# pure_midi.net
KiCad netlist of a schematic drawn in EAGLE
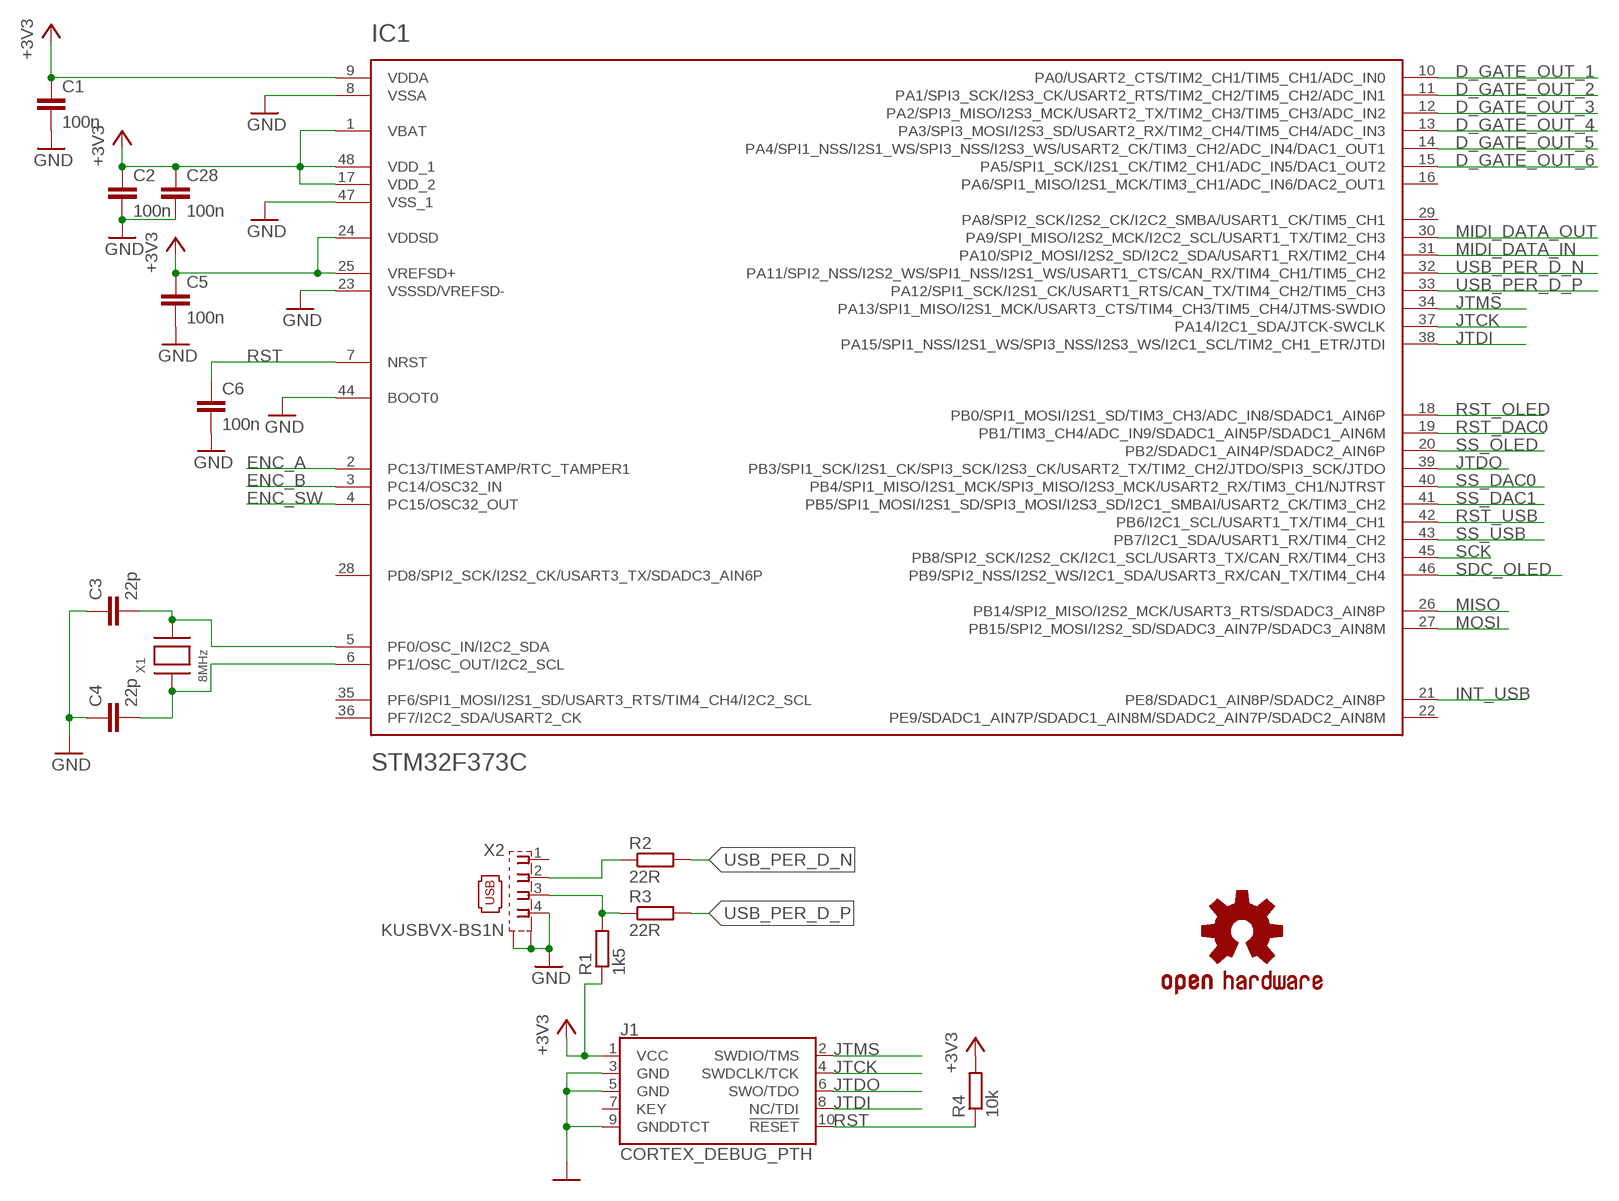
[diagram p0: schematic, sheet 1]
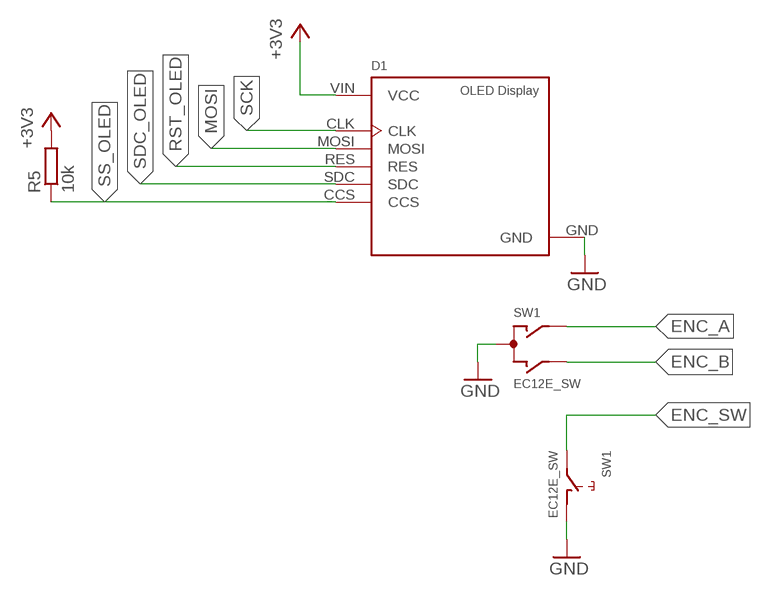
[diagram p1: schematic, sheet 2]
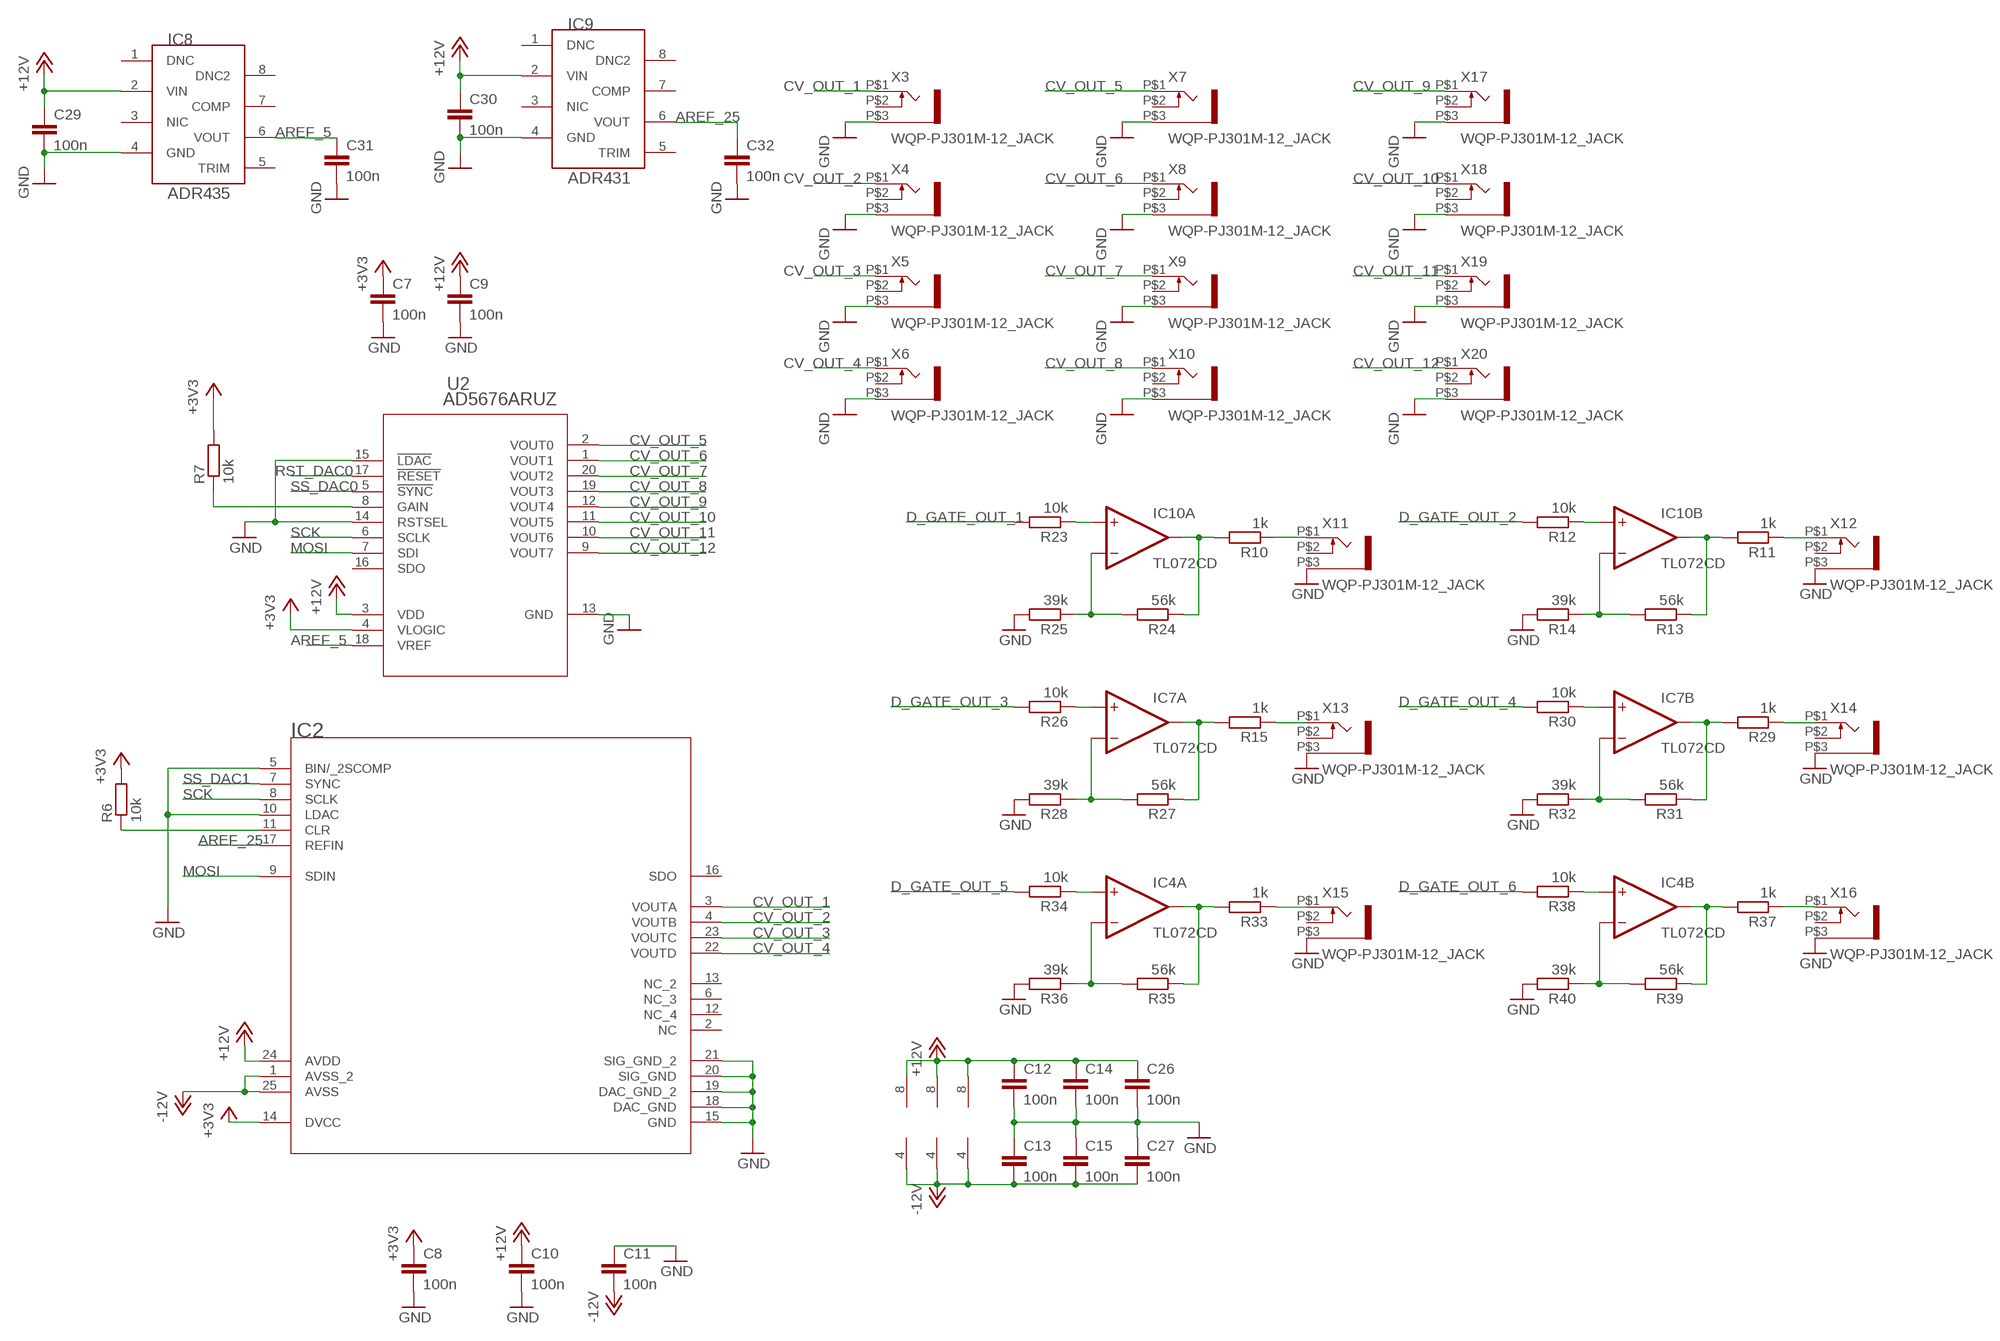
[diagram p2: schematic, sheet 3]
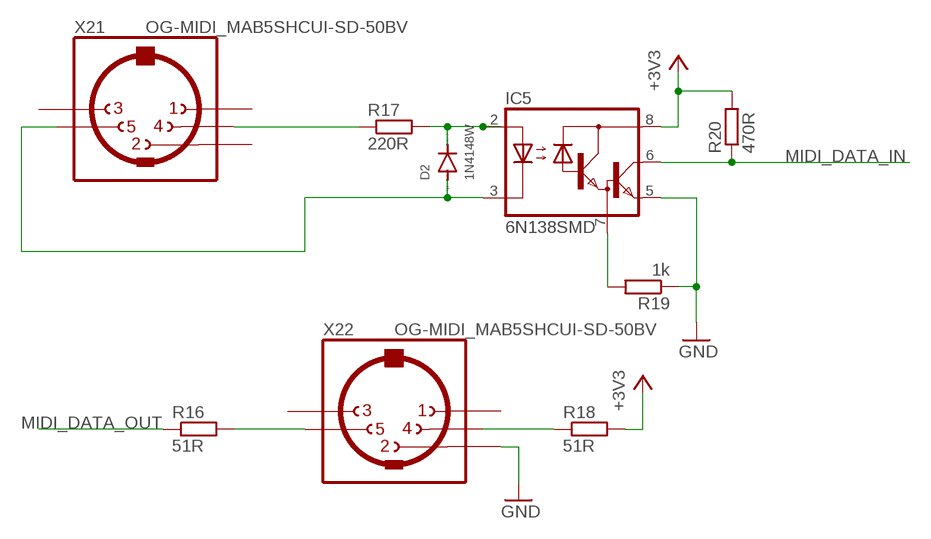
[diagram p3: schematic, sheet 4]
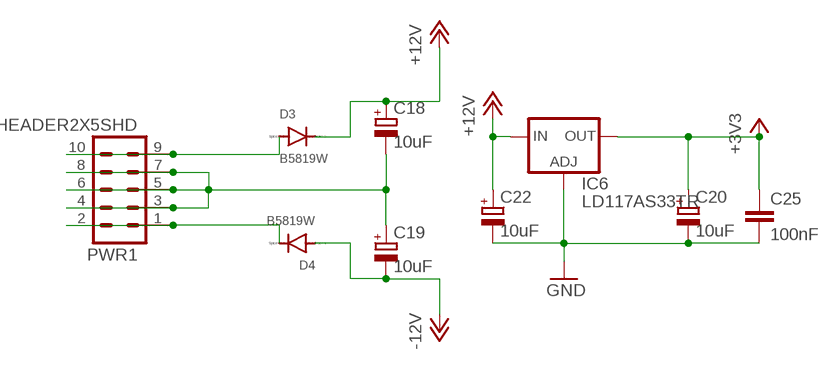
[diagram p4: schematic, sheet 5]

(export (version "E")
  (design (tool "Eeschema 10.0.6"))
  (components
    (comp (ref "C1")
      (value "100n")
      (footprint "eagle-import:C0603")
      (libsource (lib "eagle-import") (part "C-EUC0603"))
    )
    (comp (ref "C2")
      (value "100n")
      (footprint "eagle-import:C0603")
      (libsource (lib "eagle-import") (part "C-EUC0603"))
    )
    (comp (ref "C3")
      (value "22p")
      (footprint "eagle-import:C0603")
      (libsource (lib "eagle-import") (part "C-EUC0603"))
    )
    (comp (ref "C4")
      (value "22p")
      (footprint "eagle-import:C0603")
      (libsource (lib "eagle-import") (part "C-EUC0603"))
    )
    (comp (ref "C5")
      (value "100n")
      (footprint "eagle-import:C0603")
      (libsource (lib "eagle-import") (part "C-EUC0603"))
    )
    (comp (ref "C6")
      (value "100n")
      (footprint "eagle-import:C0603")
      (libsource (lib "eagle-import") (part "C-EUC0603"))
    )
    (comp (ref "C28")
      (value "100n")
      (footprint "eagle-import:C0603")
      (libsource (lib "eagle-import") (part "C-EUC0603"))
    )
    (comp (ref "IC1")
      (value "STM32F373C")
      (footprint "eagle-import:LQFP48")
      (libsource (lib "eagle-import") (part "STM32F373C"))
    )
    (comp (ref "J1")
      (value "CORTEX_DEBUG_PTH")
      (footprint "eagle-import:2X5-PTH-1.27MM")
      (libsource (lib "eagle-import") (part "CORTEX_DEBUG_PTH"))
    )
    (comp (ref "LOGO1")
      (value "OSHW-LOGOM")
      (footprint "eagle-import:OSHW-LOGO-M")
      (libsource (lib "eagle-import") (part "OSHW-LOGOM"))
    )
    (comp (ref "R1")
      (value "1k5")
      (footprint "eagle-import:R0603")
      (libsource (lib "eagle-import") (part "R-EU_R0603"))
    )
    (comp (ref "R2")
      (value "22R")
      (footprint "eagle-import:R0603")
      (libsource (lib "eagle-import") (part "R-EU_R0603"))
    )
    (comp (ref "R3")
      (value "22R")
      (footprint "eagle-import:R0603")
      (libsource (lib "eagle-import") (part "R-EU_R0603"))
    )
    (comp (ref "R4")
      (value "10k")
      (footprint "eagle-import:R0603")
      (libsource (lib "eagle-import") (part "R-EU_R0603"))
    )
    (comp (ref "X1")
      (value "8MHz")
      (footprint "eagle-import:NX5032")
      (libsource (lib "eagle-import") (part "XTALNX5032"))
    )
    (comp (ref "X2")
      (value "KUSBVX-BS1N")
      (footprint "eagle-import:KUSBVX-BS1N")
      (libsource (lib "eagle-import") (part "KUSBVX-BS1N"))
    )
    (comp (ref "D1")
      (value "OLED_1.3_128X64_SPI")
      (footprint "eagle-import:C1_ADAFRUIT_1.3_128X64_OLED")
      (libsource (lib "eagle-import") (part "OLED_1.3_128X64_SPI"))
    )
    (comp (ref "R5")
      (value "10k")
      (footprint "eagle-import:R0603")
      (libsource (lib "eagle-import") (part "R-EU_R0603"))
    )
    (comp (ref "SW1")
      (value "EC12E_SW")
      (footprint "eagle-import:ALPS_EC12E_SW")
      (fields (field (name "MPN") "EC12E2424407"))
      (libsource (lib "eagle-import") (part "EC12E_SW"))
    )
    (comp (ref "C7")
      (value "100n")
      (footprint "eagle-import:C0603")
      (libsource (lib "eagle-import") (part "C-EUC0603"))
    )
    (comp (ref "C8")
      (value "100n")
      (footprint "eagle-import:C0603")
      (libsource (lib "eagle-import") (part "C-EUC0603"))
    )
    (comp (ref "C9")
      (value "100n")
      (footprint "eagle-import:C0603")
      (libsource (lib "eagle-import") (part "C-EUC0603"))
    )
    (comp (ref "C10")
      (value "100n")
      (footprint "eagle-import:C0603")
      (libsource (lib "eagle-import") (part "C-EUC0603"))
    )
    (comp (ref "C11")
      (value "100n")
      (footprint "eagle-import:C0603")
      (libsource (lib "eagle-import") (part "C-EUC0603"))
    )
    (comp (ref "C12")
      (value "100n")
      (footprint "eagle-import:C0603")
      (libsource (lib "eagle-import") (part "C-EUC0603"))
    )
    (comp (ref "C13")
      (value "100n")
      (footprint "eagle-import:C0603")
      (libsource (lib "eagle-import") (part "C-EUC0603"))
    )
    (comp (ref "C14")
      (value "100n")
      (footprint "eagle-import:C0603")
      (libsource (lib "eagle-import") (part "C-EUC0603"))
    )
    (comp (ref "C15")
      (value "100n")
      (footprint "eagle-import:C0603")
      (libsource (lib "eagle-import") (part "C-EUC0603"))
    )
    (comp (ref "C26")
      (value "100n")
      (footprint "eagle-import:C0603")
      (libsource (lib "eagle-import") (part "C-EUC0603"))
    )
    (comp (ref "C27")
      (value "100n")
      (footprint "eagle-import:C0603")
      (libsource (lib "eagle-import") (part "C-EUC0603"))
    )
    (comp (ref "C29")
      (value "100n")
      (footprint "eagle-import:C0603")
      (libsource (lib "eagle-import") (part "C-EUC0603"))
    )
    (comp (ref "C30")
      (value "100n")
      (footprint "eagle-import:C0603")
      (libsource (lib "eagle-import") (part "C-EUC0603"))
    )
    (comp (ref "C31")
      (value "100n")
      (footprint "eagle-import:C0603")
      (libsource (lib "eagle-import") (part "C-EUC0603"))
    )
    (comp (ref "C32")
      (value "100n")
      (footprint "eagle-import:C0603")
      (libsource (lib "eagle-import") (part "C-EUC0603"))
    )
    (comp (ref "IC2")
      (value "AD5754BREZ")
      (footprint "eagle-import:RE_24")
      (libsource (lib "eagle-import") (part "AD5754BREZ"))
    )
    (comp (ref "IC4")
      (value "TL072CD")
      (footprint "eagle-import:SOIC8")
      (libsource (lib "eagle-import") (part "TL072DC"))
    )
    (comp (ref "IC7")
      (value "TL072CD")
      (footprint "eagle-import:SOIC8")
      (libsource (lib "eagle-import") (part "TL072DC"))
    )
    (comp (ref "IC8")
      (value "ADR435")
      (footprint "eagle-import:MSOP8")
      (libsource (lib "eagle-import") (part "ADR43XXRMZ"))
    )
    (comp (ref "IC9")
      (value "ADR431")
      (footprint "eagle-import:MSOP8")
      (libsource (lib "eagle-import") (part "ADR43XXRMZ"))
    )
    (comp (ref "IC10")
      (value "TL072CD")
      (footprint "eagle-import:SOIC8")
      (libsource (lib "eagle-import") (part "TL072DC"))
    )
    (comp (ref "R6")
      (value "10k")
      (footprint "eagle-import:R0603")
      (libsource (lib "eagle-import") (part "R-EU_R0603"))
    )
    (comp (ref "R7")
      (value "10k")
      (footprint "eagle-import:R0603")
      (libsource (lib "eagle-import") (part "R-EU_R0603"))
    )
    (comp (ref "R10")
      (value "1k")
      (footprint "eagle-import:R0603")
      (libsource (lib "eagle-import") (part "R-EU_R0603"))
    )
    (comp (ref "R11")
      (value "1k")
      (footprint "eagle-import:R0603")
      (libsource (lib "eagle-import") (part "R-EU_R0603"))
    )
    (comp (ref "R12")
      (value "10k")
      (footprint "eagle-import:R0603")
      (libsource (lib "eagle-import") (part "R-EU_R0603"))
    )
    (comp (ref "R13")
      (value "56k")
      (footprint "eagle-import:R0603")
      (libsource (lib "eagle-import") (part "R-EU_R0603"))
    )
    (comp (ref "R14")
      (value "39k")
      (footprint "eagle-import:R0603")
      (libsource (lib "eagle-import") (part "R-EU_R0603"))
    )
    (comp (ref "R15")
      (value "1k")
      (footprint "eagle-import:R0603")
      (libsource (lib "eagle-import") (part "R-EU_R0603"))
    )
    (comp (ref "R23")
      (value "10k")
      (footprint "eagle-import:R0603")
      (libsource (lib "eagle-import") (part "R-EU_R0603"))
    )
    (comp (ref "R24")
      (value "56k")
      (footprint "eagle-import:R0603")
      (libsource (lib "eagle-import") (part "R-EU_R0603"))
    )
    (comp (ref "R25")
      (value "39k")
      (footprint "eagle-import:R0603")
      (libsource (lib "eagle-import") (part "R-EU_R0603"))
    )
    (comp (ref "R26")
      (value "10k")
      (footprint "eagle-import:R0603")
      (libsource (lib "eagle-import") (part "R-EU_R0603"))
    )
    (comp (ref "R27")
      (value "56k")
      (footprint "eagle-import:R0603")
      (libsource (lib "eagle-import") (part "R-EU_R0603"))
    )
    (comp (ref "R28")
      (value "39k")
      (footprint "eagle-import:R0603")
      (libsource (lib "eagle-import") (part "R-EU_R0603"))
    )
    (comp (ref "R29")
      (value "1k")
      (footprint "eagle-import:R0603")
      (libsource (lib "eagle-import") (part "R-EU_R0603"))
    )
    (comp (ref "R30")
      (value "10k")
      (footprint "eagle-import:R0603")
      (libsource (lib "eagle-import") (part "R-EU_R0603"))
    )
    (comp (ref "R31")
      (value "56k")
      (footprint "eagle-import:R0603")
      (libsource (lib "eagle-import") (part "R-EU_R0603"))
    )
    (comp (ref "R32")
      (value "39k")
      (footprint "eagle-import:R0603")
      (libsource (lib "eagle-import") (part "R-EU_R0603"))
    )
    (comp (ref "R33")
      (value "1k")
      (footprint "eagle-import:R0603")
      (libsource (lib "eagle-import") (part "R-EU_R0603"))
    )
    (comp (ref "R34")
      (value "10k")
      (footprint "eagle-import:R0603")
      (libsource (lib "eagle-import") (part "R-EU_R0603"))
    )
    (comp (ref "R35")
      (value "56k")
      (footprint "eagle-import:R0603")
      (libsource (lib "eagle-import") (part "R-EU_R0603"))
    )
    (comp (ref "R36")
      (value "39k")
      (footprint "eagle-import:R0603")
      (libsource (lib "eagle-import") (part "R-EU_R0603"))
    )
    (comp (ref "R37")
      (value "1k")
      (footprint "eagle-import:R0603")
      (libsource (lib "eagle-import") (part "R-EU_R0603"))
    )
    (comp (ref "R38")
      (value "10k")
      (footprint "eagle-import:R0603")
      (libsource (lib "eagle-import") (part "R-EU_R0603"))
    )
    (comp (ref "R39")
      (value "56k")
      (footprint "eagle-import:R0603")
      (libsource (lib "eagle-import") (part "R-EU_R0603"))
    )
    (comp (ref "R40")
      (value "39k")
      (footprint "eagle-import:R0603")
      (libsource (lib "eagle-import") (part "R-EU_R0603"))
    )
    (comp (ref "U2")
      (value "AD5676ARUZ")
      (footprint "eagle-import:RU_20")
      (libsource (lib "eagle-import") (part "AD5676ARUZ"))
    )
    (comp (ref "X3")
      (value "WQP-PJ301M-12_JACK")
      (footprint "eagle-import:WQP-PJ301M-12_JACK")
      (libsource (lib "eagle-import") (part "WQP-PJ301M-12_JACK"))
    )
    (comp (ref "X4")
      (value "WQP-PJ301M-12_JACK")
      (footprint "eagle-import:WQP-PJ301M-12_JACK")
      (libsource (lib "eagle-import") (part "WQP-PJ301M-12_JACK"))
    )
    (comp (ref "X5")
      (value "WQP-PJ301M-12_JACK")
      (footprint "eagle-import:WQP-PJ301M-12_JACK")
      (libsource (lib "eagle-import") (part "WQP-PJ301M-12_JACK"))
    )
    (comp (ref "X6")
      (value "WQP-PJ301M-12_JACK")
      (footprint "eagle-import:WQP-PJ301M-12_JACK")
      (libsource (lib "eagle-import") (part "WQP-PJ301M-12_JACK"))
    )
    (comp (ref "X7")
      (value "WQP-PJ301M-12_JACK")
      (footprint "eagle-import:WQP-PJ301M-12_JACK")
      (libsource (lib "eagle-import") (part "WQP-PJ301M-12_JACK"))
    )
    (comp (ref "X8")
      (value "WQP-PJ301M-12_JACK")
      (footprint "eagle-import:WQP-PJ301M-12_JACK")
      (libsource (lib "eagle-import") (part "WQP-PJ301M-12_JACK"))
    )
    (comp (ref "X9")
      (value "WQP-PJ301M-12_JACK")
      (footprint "eagle-import:WQP-PJ301M-12_JACK")
      (libsource (lib "eagle-import") (part "WQP-PJ301M-12_JACK"))
    )
    (comp (ref "X10")
      (value "WQP-PJ301M-12_JACK")
      (footprint "eagle-import:WQP-PJ301M-12_JACK")
      (libsource (lib "eagle-import") (part "WQP-PJ301M-12_JACK"))
    )
    (comp (ref "X11")
      (value "WQP-PJ301M-12_JACK")
      (footprint "eagle-import:WQP-PJ301M-12_JACK")
      (libsource (lib "eagle-import") (part "WQP-PJ301M-12_JACK"))
    )
    (comp (ref "X12")
      (value "WQP-PJ301M-12_JACK")
      (footprint "eagle-import:WQP-PJ301M-12_JACK")
      (libsource (lib "eagle-import") (part "WQP-PJ301M-12_JACK"))
    )
    (comp (ref "X13")
      (value "WQP-PJ301M-12_JACK")
      (footprint "eagle-import:WQP-PJ301M-12_JACK")
      (libsource (lib "eagle-import") (part "WQP-PJ301M-12_JACK"))
    )
    (comp (ref "X14")
      (value "WQP-PJ301M-12_JACK")
      (footprint "eagle-import:WQP-PJ301M-12_JACK")
      (libsource (lib "eagle-import") (part "WQP-PJ301M-12_JACK"))
    )
    (comp (ref "X15")
      (value "WQP-PJ301M-12_JACK")
      (footprint "eagle-import:WQP-PJ301M-12_JACK")
      (libsource (lib "eagle-import") (part "WQP-PJ301M-12_JACK"))
    )
    (comp (ref "X16")
      (value "WQP-PJ301M-12_JACK")
      (footprint "eagle-import:WQP-PJ301M-12_JACK")
      (libsource (lib "eagle-import") (part "WQP-PJ301M-12_JACK"))
    )
    (comp (ref "X17")
      (value "WQP-PJ301M-12_JACK")
      (footprint "eagle-import:WQP-PJ301M-12_JACK")
      (libsource (lib "eagle-import") (part "WQP-PJ301M-12_JACK"))
    )
    (comp (ref "X18")
      (value "WQP-PJ301M-12_JACK")
      (footprint "eagle-import:WQP-PJ301M-12_JACK")
      (libsource (lib "eagle-import") (part "WQP-PJ301M-12_JACK"))
    )
    (comp (ref "X19")
      (value "WQP-PJ301M-12_JACK")
      (footprint "eagle-import:WQP-PJ301M-12_JACK")
      (libsource (lib "eagle-import") (part "WQP-PJ301M-12_JACK"))
    )
    (comp (ref "X20")
      (value "WQP-PJ301M-12_JACK")
      (footprint "eagle-import:WQP-PJ301M-12_JACK")
      (libsource (lib "eagle-import") (part "WQP-PJ301M-12_JACK"))
    )
    (comp (ref "D2")
      (value "1N4148W")
      (footprint "eagle-import:SOD123")
      (libsource (lib "eagle-import") (part "DIODE-SOD123"))
    )
    (comp (ref "IC5")
      (value "6N138SMD")
      (footprint "eagle-import:SO8-GW300")
      (libsource (lib "eagle-import") (part "6N138SMD"))
    )
    (comp (ref "R16")
      (value "51R")
      (footprint "eagle-import:R0603")
      (libsource (lib "eagle-import") (part "R-EU_R0603"))
    )
    (comp (ref "R17")
      (value "220R")
      (footprint "eagle-import:R0603")
      (libsource (lib "eagle-import") (part "R-EU_R0603"))
    )
    (comp (ref "R18")
      (value "51R")
      (footprint "eagle-import:R0603")
      (libsource (lib "eagle-import") (part "R-EU_R0603"))
    )
    (comp (ref "R19")
      (value "1k")
      (footprint "eagle-import:R0603")
      (libsource (lib "eagle-import") (part "R-EU_R0603"))
    )
    (comp (ref "R20")
      (value "470R")
      (footprint "eagle-import:R0603")
      (libsource (lib "eagle-import") (part "R-EU_R0603"))
    )
    (comp (ref "X21")
      (value "OG-MIDI_MAB5SHCUI-SD-50BV")
      (footprint "eagle-import:OG-MIDI_SD-50BV")
      (libsource (lib "eagle-import") (part "OG-MIDI_MAB5SHCUI-SD-50BV"))
    )
    (comp (ref "X22")
      (value "OG-MIDI_MAB5SHCUI-SD-50BV")
      (footprint "eagle-import:OG-MIDI_SD-50BV")
      (libsource (lib "eagle-import") (part "OG-MIDI_MAB5SHCUI-SD-50BV"))
    )
    (comp (ref "C18")
      (value "10uF")
      (footprint "eagle-import:CASE-A_3216")
      (libsource (lib "eagle-import") (part "CPOL-EUA/3216-18R"))
    )
    (comp (ref "C19")
      (value "10uF")
      (footprint "eagle-import:CASE-A_3216")
      (libsource (lib "eagle-import") (part "CPOL-EUA/3216-18R"))
    )
    (comp (ref "C20")
      (value "10uF")
      (footprint "eagle-import:CASE-A_3216")
      (libsource (lib "eagle-import") (part "CPOL-EUA/3216-18R"))
    )
    (comp (ref "C22")
      (value "10uF")
      (footprint "eagle-import:CASE-A_3216")
      (libsource (lib "eagle-import") (part "CPOL-EUA/3216-18R"))
    )
    (comp (ref "C25")
      (value "100nF")
      (footprint "eagle-import:C0603")
      (libsource (lib "eagle-import") (part "C-EUC0603"))
    )
    (comp (ref "D3")
      (value "B5819W")
      (footprint "eagle-import:SOD123")
      (libsource (lib "eagle-import") (part "DIODE-SOD123"))
    )
    (comp (ref "D4")
      (value "B5819W")
      (footprint "eagle-import:SOD123")
      (libsource (lib "eagle-import") (part "DIODE-SOD123"))
    )
    (comp (ref "IC6")
      (value "LD117AS33TR")
      (footprint "eagle-import:SOT223")
      (libsource (lib "eagle-import") (part "LD117A?S33TR"))
    )
    (comp (ref "PWR1")
      (value "HEADER2X5SHD")
      (footprint "eagle-import:2X5-SHROUDED")
      (libsource (lib "eagle-import") (part "HEADER2X5SHD"))
    )
  )
  (nets
    (net (code "1") (name "+3V3") (class "Default")
      (node (ref "C1") (pin "1") (pinfunction "1_1") (pintype "passive"))
      (node (ref "C2") (pin "1") (pinfunction "1_1") (pintype "passive"))
      (node (ref "C20") (pin "+") (pinfunction "+_+") (pintype "passive"))
      (node (ref "C25") (pin "1") (pinfunction "1_1") (pintype "passive"))
      (node (ref "C28") (pin "1") (pinfunction "1_1") (pintype "passive"))
      (node (ref "C5") (pin "1") (pinfunction "1_1") (pintype "passive"))
      (node (ref "C7") (pin "1") (pinfunction "1_1") (pintype "passive"))
      (node (ref "C8") (pin "1") (pinfunction "1_1") (pintype "passive"))
      (node (ref "D1") (pin "VIN") (pinfunction "VCC_VIN") (pintype "power_in"))
      (node (ref "IC1") (pin "1") (pinfunction "VBAT_1") (pintype "power_in"))
      (node (ref "IC1") (pin "17") (pinfunction "VDD_2_17") (pintype "power_in"))
      (node (ref "IC1") (pin "24") (pinfunction "VDDSD_24") (pintype "power_in"))
      (node (ref "IC1") (pin "25") (pinfunction "VREFSD+_25") (pintype "power_in"))
      (node (ref "IC1") (pin "48") (pinfunction "VDD_1_48") (pintype "power_in"))
      (node (ref "IC1") (pin "9") (pinfunction "VDDA_9") (pintype "power_in"))
      (node (ref "IC2") (pin "14") (pinfunction "DVCC_14") (pintype "power_in"))
      (node (ref "IC5") (pin "8") (pinfunction "VCC_8") (pintype "passive"))
      (node (ref "IC6") (pin "4") (pinfunction "OUT_4") (pintype "passive"))
      (node (ref "J1") (pin "1") (pinfunction "VCC_1") (pintype "bidirectional"))
      (node (ref "R1") (pin "1") (pinfunction "1_1") (pintype "passive"))
      (node (ref "R18") (pin "2") (pinfunction "2_2") (pintype "passive"))
      (node (ref "R20") (pin "2") (pinfunction "2_2") (pintype "passive"))
      (node (ref "R4") (pin "2") (pinfunction "2_2") (pintype "passive"))
      (node (ref "R5") (pin "2") (pinfunction "2_2") (pintype "passive"))
      (node (ref "R6") (pin "2") (pinfunction "2_2") (pintype "passive"))
      (node (ref "R7") (pin "2") (pinfunction "2_2") (pintype "passive"))
      (node (ref "U2") (pin "4") (pinfunction "VLOGIC_4") (pintype "passive"))
    )
    (net (code "2") (name "+12V") (class "Default")
      (node (ref "C10") (pin "1") (pinfunction "1_1") (pintype "passive"))
      (node (ref "C12") (pin "1") (pinfunction "1_1") (pintype "passive"))
      (node (ref "C14") (pin "1") (pinfunction "1_1") (pintype "passive"))
      (node (ref "C18") (pin "+") (pinfunction "+_+") (pintype "passive"))
      (node (ref "C22") (pin "+") (pinfunction "+_+") (pintype "passive"))
      (node (ref "C26") (pin "1") (pinfunction "1_1") (pintype "passive"))
      (node (ref "C29") (pin "1") (pinfunction "1_1") (pintype "passive"))
      (node (ref "C30") (pin "1") (pinfunction "1_1") (pintype "passive"))
      (node (ref "C9") (pin "1") (pinfunction "1_1") (pintype "passive"))
      (node (ref "D3") (pin "C") (pinfunction "C_C") (pintype "passive"))
      (node (ref "IC10") (pin "8") (pinfunction "V+_8") (pintype "power_in"))
      (node (ref "IC2") (pin "24") (pinfunction "AVDD_24") (pintype "power_in"))
      (node (ref "IC4") (pin "8") (pinfunction "V+_8") (pintype "power_in"))
      (node (ref "IC6") (pin "3") (pinfunction "IN_3") (pintype "input"))
      (node (ref "IC7") (pin "8") (pinfunction "V+_8") (pintype "power_in"))
      (node (ref "IC8") (pin "2") (pinfunction "VIN_2") (pintype "power_in"))
      (node (ref "IC9") (pin "2") (pinfunction "VIN_2") (pintype "power_in"))
      (node (ref "U2") (pin "3") (pinfunction "VDD_3") (pintype "passive"))
    )
    (net (code "3") (name "-12V") (class "Default")
      (node (ref "C11") (pin "2") (pinfunction "2_2") (pintype "passive"))
      (node (ref "C13") (pin "2") (pinfunction "2_2") (pintype "passive"))
      (node (ref "C15") (pin "2") (pinfunction "2_2") (pintype "passive"))
      (node (ref "C19") (pin "-") (pinfunction "-_-") (pintype "passive"))
      (node (ref "C27") (pin "2") (pinfunction "2_2") (pintype "passive"))
      (node (ref "D4") (pin "A") (pinfunction "A_A") (pintype "passive"))
      (node (ref "IC10") (pin "4") (pinfunction "V-_4") (pintype "power_in"))
      (node (ref "IC2") (pin "1") (pinfunction "AVSS_2_1") (pintype "passive"))
      (node (ref "IC2") (pin "25") (pinfunction "AVSS_25") (pintype "power_in"))
      (node (ref "IC4") (pin "4") (pinfunction "V-_4") (pintype "power_in"))
      (node (ref "IC7") (pin "4") (pinfunction "V-_4") (pintype "power_in"))
    )
    (net (code "4") (name "AREF_5") (class "Default")
      (node (ref "C31") (pin "1") (pinfunction "1_1") (pintype "passive"))
      (node (ref "IC8") (pin "6") (pinfunction "VOUT_6") (pintype "power_in"))
      (node (ref "U2") (pin "18") (pinfunction "VREF_18") (pintype "passive"))
    )
    (net (code "5") (name "AREF_25") (class "Default")
      (node (ref "C32") (pin "1") (pinfunction "1_1") (pintype "passive"))
      (node (ref "IC2") (pin "17") (pinfunction "REFIN_17") (pintype "passive"))
      (node (ref "IC9") (pin "6") (pinfunction "VOUT_6") (pintype "power_in"))
    )
    (net (code "6") (name "CV_OUT_1") (class "Default")
      (node (ref "IC2") (pin "3") (pinfunction "VOUTA_3") (pintype "passive"))
      (node (ref "X3") (pin "P$1") (pinfunction "2_P$1") (pintype "passive"))
    )
    (net (code "7") (name "CV_OUT_2") (class "Default")
      (node (ref "IC2") (pin "4") (pinfunction "VOUTB_4") (pintype "passive"))
      (node (ref "X4") (pin "P$1") (pinfunction "2_P$1") (pintype "passive"))
    )
    (net (code "8") (name "CV_OUT_3") (class "Default")
      (node (ref "IC2") (pin "23") (pinfunction "VOUTC_23") (pintype "passive"))
      (node (ref "X5") (pin "P$1") (pinfunction "2_P$1") (pintype "passive"))
    )
    (net (code "9") (name "CV_OUT_4") (class "Default")
      (node (ref "IC2") (pin "22") (pinfunction "VOUTD_22") (pintype "passive"))
      (node (ref "X6") (pin "P$1") (pinfunction "2_P$1") (pintype "passive"))
    )
    (net (code "10") (name "CV_OUT_5") (class "Default")
      (node (ref "U2") (pin "2") (pinfunction "VOUT0_2") (pintype "passive"))
      (node (ref "X7") (pin "P$1") (pinfunction "2_P$1") (pintype "passive"))
    )
    (net (code "11") (name "CV_OUT_6") (class "Default")
      (node (ref "U2") (pin "1") (pinfunction "VOUT1_1") (pintype "passive"))
      (node (ref "X8") (pin "P$1") (pinfunction "2_P$1") (pintype "passive"))
    )
    (net (code "12") (name "CV_OUT_7") (class "Default")
      (node (ref "U2") (pin "20") (pinfunction "VOUT2_20") (pintype "passive"))
      (node (ref "X9") (pin "P$1") (pinfunction "2_P$1") (pintype "passive"))
    )
    (net (code "13") (name "CV_OUT_8") (class "Default")
      (node (ref "U2") (pin "19") (pinfunction "VOUT3_19") (pintype "passive"))
      (node (ref "X10") (pin "P$1") (pinfunction "2_P$1") (pintype "passive"))
    )
    (net (code "14") (name "CV_OUT_9") (class "Default")
      (node (ref "U2") (pin "12") (pinfunction "VOUT4_12") (pintype "passive"))
      (node (ref "X17") (pin "P$1") (pinfunction "2_P$1") (pintype "passive"))
    )
    (net (code "15") (name "CV_OUT_10") (class "Default")
      (node (ref "U2") (pin "11") (pinfunction "VOUT5_11") (pintype "passive"))
      (node (ref "X18") (pin "P$1") (pinfunction "2_P$1") (pintype "passive"))
    )
    (net (code "16") (name "CV_OUT_11") (class "Default")
      (node (ref "U2") (pin "10") (pinfunction "VOUT6_10") (pintype "passive"))
      (node (ref "X19") (pin "P$1") (pinfunction "2_P$1") (pintype "passive"))
    )
    (net (code "17") (name "CV_OUT_12") (class "Default")
      (node (ref "U2") (pin "9") (pinfunction "VOUT7_9") (pintype "passive"))
      (node (ref "X20") (pin "P$1") (pinfunction "2_P$1") (pintype "passive"))
    )
    (net (code "18") (name "D_GATE_OUT_1") (class "Default")
      (node (ref "IC1") (pin "10") (pinfunction "PA0/USART2_CTS/TIM2_CH1/TIM5_CH1/ADC_IN0_10") (pintype "bidirectional"))
      (node (ref "R23") (pin "2") (pinfunction "2_2") (pintype "passive"))
    )
    (net (code "19") (name "D_GATE_OUT_2") (class "Default")
      (node (ref "IC1") (pin "11") (pinfunction "PA1/SPI3_SCK/I2S3_CK/USART2_RTS/TIM2_CH2/TIM5_CH2/ADC_IN1_11") (pintype "bidirectional"))
      (node (ref "R12") (pin "2") (pinfunction "2_2") (pintype "passive"))
    )
    (net (code "20") (name "D_GATE_OUT_3") (class "Default")
      (node (ref "IC1") (pin "12") (pinfunction "PA2/SPI3_MISO/I2S3_MCK/USART2_TX/TIM2_CH3/TIM5_CH3/ADC_IN2_12") (pintype "bidirectional"))
      (node (ref "R26") (pin "2") (pinfunction "2_2") (pintype "passive"))
    )
    (net (code "21") (name "D_GATE_OUT_4") (class "Default")
      (node (ref "IC1") (pin "13") (pinfunction "PA3/SPI3_MOSI/I2S3_SD/USART2_RX/TIM2_CH4/TIM5_CH4/ADC_IN3_13") (pintype "bidirectional"))
      (node (ref "R30") (pin "2") (pinfunction "2_2") (pintype "passive"))
    )
    (net (code "22") (name "D_GATE_OUT_5") (class "Default")
      (node (ref "IC1") (pin "14") (pinfunction "PA4/SPI1_NSS/I2S1_WS/SPI3_NSS/I2S3_WS/USART2_CK/TIM3_CH2/ADC_IN4/DAC1_OUT1_14") (pintype "bidirectional"))
      (node (ref "R34") (pin "2") (pinfunction "2_2") (pintype "passive"))
    )
    (net (code "23") (name "D_GATE_OUT_6") (class "Default")
      (node (ref "IC1") (pin "15") (pinfunction "PA5/SPI1_SCK/I2S1_CK/TIM2_CH1/ADC_IN5/DAC1_OUT2_15") (pintype "bidirectional"))
      (node (ref "R38") (pin "2") (pinfunction "2_2") (pintype "passive"))
    )
    (net (code "24") (name "ENC_A") (class "Default")
      (node (ref "IC1") (pin "2") (pinfunction "PC13/TIMESTAMP/RTC_TAMPER1_2") (pintype "bidirectional"))
      (node (ref "SW1") (pin "A") (pinfunction "A_A") (pintype "passive"))
    )
    (net (code "25") (name "ENC_B") (class "Default")
      (node (ref "IC1") (pin "3") (pinfunction "PC14/OSC32_IN_3") (pintype "bidirectional"))
      (node (ref "SW1") (pin "B") (pinfunction "B_B") (pintype "passive"))
    )
    (net (code "26") (name "ENC_SW") (class "Default")
      (node (ref "IC1") (pin "4") (pinfunction "PC15/OSC32_OUT_4") (pintype "bidirectional"))
      (node (ref "SW1") (pin "E") (pinfunction "2_E") (pintype "passive"))
    )
    (net (code "27") (name "GND") (class "Default")
      (node (ref "C1") (pin "2") (pinfunction "2_2") (pintype "passive"))
      (node (ref "C10") (pin "2") (pinfunction "2_2") (pintype "passive"))
      (node (ref "C11") (pin "1") (pinfunction "1_1") (pintype "passive"))
      (node (ref "C12") (pin "2") (pinfunction "2_2") (pintype "passive"))
      (node (ref "C13") (pin "1") (pinfunction "1_1") (pintype "passive"))
      (node (ref "C14") (pin "2") (pinfunction "2_2") (pintype "passive"))
      (node (ref "C15") (pin "1") (pinfunction "1_1") (pintype "passive"))
      (node (ref "C2") (pin "2") (pinfunction "2_2") (pintype "passive"))
      (node (ref "C20") (pin "-") (pinfunction "-_-") (pintype "passive"))
      (node (ref "C22") (pin "-") (pinfunction "-_-") (pintype "passive"))
      (node (ref "C25") (pin "2") (pinfunction "2_2") (pintype "passive"))
      (node (ref "C26") (pin "2") (pinfunction "2_2") (pintype "passive"))
      (node (ref "C27") (pin "1") (pinfunction "1_1") (pintype "passive"))
      (node (ref "C28") (pin "2") (pinfunction "2_2") (pintype "passive"))
      (node (ref "C29") (pin "2") (pinfunction "2_2") (pintype "passive"))
      (node (ref "C3") (pin "1") (pinfunction "1_1") (pintype "passive"))
      (node (ref "C30") (pin "2") (pinfunction "2_2") (pintype "passive"))
      (node (ref "C31") (pin "2") (pinfunction "2_2") (pintype "passive"))
      (node (ref "C32") (pin "2") (pinfunction "2_2") (pintype "passive"))
      (node (ref "C4") (pin "1") (pinfunction "1_1") (pintype "passive"))
      (node (ref "C5") (pin "2") (pinfunction "2_2") (pintype "passive"))
      (node (ref "C6") (pin "2") (pinfunction "2_2") (pintype "passive"))
      (node (ref "C7") (pin "2") (pinfunction "2_2") (pintype "passive"))
      (node (ref "C8") (pin "2") (pinfunction "2_2") (pintype "passive"))
      (node (ref "C9") (pin "2") (pinfunction "2_2") (pintype "passive"))
      (node (ref "D1") (pin "GND") (pinfunction "GND_GND") (pintype "power_in"))
      (node (ref "IC1") (pin "23") (pinfunction "VSSSD/VREFSD-_23") (pintype "power_in"))
      (node (ref "IC1") (pin "44") (pinfunction "BOOT0_44") (pintype "bidirectional"))
      (node (ref "IC1") (pin "47") (pinfunction "VSS_1_47") (pintype "power_in"))
      (node (ref "IC1") (pin "8") (pinfunction "VSSA_8") (pintype "power_in"))
      (node (ref "IC2") (pin "10") (pinfunction "LDAC_10") (pintype "passive"))
      (node (ref "IC2") (pin "15") (pinfunction "GND_15") (pintype "passive"))
      (node (ref "IC2") (pin "18") (pinfunction "DAC_GND_18") (pintype "passive"))
      (node (ref "IC2") (pin "19") (pinfunction "DAC_GND_2_19") (pintype "passive"))
      (node (ref "IC2") (pin "20") (pinfunction "SIG_GND_20") (pintype "passive"))
      (node (ref "IC2") (pin "21") (pinfunction "SIG_GND_2_21") (pintype "passive"))
      (node (ref "IC2") (pin "5") (pinfunction "BIN/_2SCOMP_5") (pintype "passive"))
      (node (ref "IC5") (pin "5") (pinfunction "GND_5") (pintype "passive"))
      (node (ref "IC6") (pin "1") (pinfunction "ADJ_1") (pintype "input"))
      (node (ref "IC8") (pin "4") (pinfunction "GND_4") (pintype "power_in"))
      (node (ref "IC9") (pin "4") (pinfunction "GND_4") (pintype "power_in"))
      (node (ref "J1") (pin "3") (pinfunction "GND_3") (pintype "bidirectional"))
      (node (ref "J1") (pin "5") (pinfunction "GND_5") (pintype "bidirectional"))
      (node (ref "J1") (pin "9") (pinfunction "GNDDTCT_9") (pintype "bidirectional"))
      (node (ref "R14") (pin "2") (pinfunction "2_2") (pintype "passive"))
      (node (ref "R19") (pin "1") (pinfunction "1_1") (pintype "passive"))
      (node (ref "R25") (pin "2") (pinfunction "2_2") (pintype "passive"))
      (node (ref "R28") (pin "2") (pinfunction "2_2") (pintype "passive"))
      (node (ref "R32") (pin "2") (pinfunction "2_2") (pintype "passive"))
      (node (ref "R36") (pin "2") (pinfunction "2_2") (pintype "passive"))
      (node (ref "R40") (pin "2") (pinfunction "2_2") (pintype "passive"))
      (node (ref "SW1") (pin "C") (pinfunction "C_C") (pintype "passive"))
      (node (ref "SW1") (pin "D") (pinfunction "1_D") (pintype "passive"))
      (node (ref "U2") (pin "13") (pinfunction "GND_13") (pintype "passive"))
      (node (ref "U2") (pin "14") (pinfunction "RSTSEL_14") (pintype "passive"))
      (node (ref "U2") (pin "15") (pinfunction "~{LDAC}_15") (pintype "passive"))
      (node (ref "X10") (pin "P$3") (pinfunction "1_P$3") (pintype "passive"))
      (node (ref "X11") (pin "P$3") (pinfunction "1_P$3") (pintype "passive"))
      (node (ref "X12") (pin "P$3") (pinfunction "1_P$3") (pintype "passive"))
      (node (ref "X13") (pin "P$3") (pinfunction "1_P$3") (pintype "passive"))
      (node (ref "X14") (pin "P$3") (pinfunction "1_P$3") (pintype "passive"))
      (node (ref "X15") (pin "P$3") (pinfunction "1_P$3") (pintype "passive"))
      (node (ref "X16") (pin "P$3") (pinfunction "1_P$3") (pintype "passive"))
      (node (ref "X17") (pin "P$3") (pinfunction "1_P$3") (pintype "passive"))
      (node (ref "X18") (pin "P$3") (pinfunction "1_P$3") (pintype "passive"))
      (node (ref "X19") (pin "P$3") (pinfunction "1_P$3") (pintype "passive"))
      (node (ref "X2") (pin "4") (pinfunction "4_4") (pintype "passive"))
      (node (ref "X2") (pin "M1") (pinfunction "S1_M1") (pintype "passive"))
      (node (ref "X2") (pin "M2") (pinfunction "S2_M2") (pintype "passive"))
      (node (ref "X20") (pin "P$3") (pinfunction "1_P$3") (pintype "passive"))
      (node (ref "X22") (pin "2") (pinfunction "2_2") (pintype "passive"))
      (node (ref "X3") (pin "P$3") (pinfunction "1_P$3") (pintype "passive"))
      (node (ref "X4") (pin "P$3") (pinfunction "1_P$3") (pintype "passive"))
      (node (ref "X5") (pin "P$3") (pinfunction "1_P$3") (pintype "passive"))
      (node (ref "X6") (pin "P$3") (pinfunction "1_P$3") (pintype "passive"))
      (node (ref "X7") (pin "P$3") (pinfunction "1_P$3") (pintype "passive"))
      (node (ref "X8") (pin "P$3") (pinfunction "1_P$3") (pintype "passive"))
      (node (ref "X9") (pin "P$3") (pinfunction "1_P$3") (pintype "passive"))
    )
    (net (code "28") (name "INT_USB") (class "Default")
      (node (ref "IC1") (pin "21") (pinfunction "PE8/SDADC1_AIN8P/SDADC2_AIN8P_21") (pintype "bidirectional"))
    )
    (net (code "29") (name "JTCK") (class "Default")
      (node (ref "IC1") (pin "37") (pinfunction "PA14/I2C1_SDA/JTCK-SWCLK_37") (pintype "bidirectional"))
      (node (ref "J1") (pin "4") (pinfunction "SWDCLK/TCK_4") (pintype "bidirectional"))
    )
    (net (code "30") (name "JTDI") (class "Default")
      (node (ref "IC1") (pin "38") (pinfunction "PA15/SPI1_NSS/I2S1_WS/SPI3_NSS/I2S3_WS/I2C1_SCL/TIM2_CH1_ETR/JTDI_38") (pintype "bidirectional"))
      (node (ref "J1") (pin "8") (pinfunction "NC/TDI_8") (pintype "bidirectional"))
    )
    (net (code "31") (name "JTDO") (class "Default")
      (node (ref "IC1") (pin "39") (pinfunction "PB3/SPI1_SCK/I2S1_CK/SPI3_SCK/I2S3_CK/USART2_TX/TIM2_CH2/JTDO/SPI3_SCK/JTDO_39") (pintype "bidirectional"))
      (node (ref "J1") (pin "6") (pinfunction "SWO/TDO_6") (pintype "bidirectional"))
    )
    (net (code "32") (name "JTMS") (class "Default")
      (node (ref "IC1") (pin "34") (pinfunction "PA13/SPI1_MISO/I2S1_MCK/USART3_CTS/TIM4_CH3/TIM5_CH4/JTMS-SWDIO_34") (pintype "bidirectional"))
      (node (ref "J1") (pin "2") (pinfunction "SWDIO/TMS_2") (pintype "bidirectional"))
    )
    (net (code "33") (name "MIDI_DATA_IN") (class "Default")
      (node (ref "IC1") (pin "31") (pinfunction "PA10/SPI2_MOSI/I2S2_SD/I2C2_SDA/USART1_RX/TIM2_CH4_31") (pintype "bidirectional"))
      (node (ref "IC5") (pin "6") (pinfunction "VO_6") (pintype "passive"))
      (node (ref "R20") (pin "1") (pinfunction "1_1") (pintype "passive"))
    )
    (net (code "34") (name "MIDI_DATA_OUT") (class "Default")
      (node (ref "IC1") (pin "30") (pinfunction "PA9/SPI_MISO/I2S2_MCK/I2C2_SCL/USART1_TX/TIM2_CH3_30") (pintype "bidirectional"))
      (node (ref "R16") (pin "1") (pinfunction "1_1") (pintype "passive"))
    )
    (net (code "35") (name "MISO") (class "Default")
      (node (ref "IC1") (pin "26") (pinfunction "PB14/SPI2_MISO/I2S2_MCK/USART3_RTS/SDADC3_AIN8P_26") (pintype "bidirectional"))
    )
    (net (code "36") (name "MOSI") (class "Default")
      (node (ref "D1") (pin "MOSI") (pinfunction "MOSI_MOSI") (pintype "input"))
      (node (ref "IC1") (pin "27") (pinfunction "PB15/SPI2_MOSI/I2S2_SD/SDADC3_AIN7P/SDADC3_AIN8M_27") (pintype "bidirectional"))
      (node (ref "IC2") (pin "9") (pinfunction "SDIN_9") (pintype "passive"))
      (node (ref "U2") (pin "7") (pinfunction "SDI_7") (pintype "passive"))
    )
    (net (code "37") (name "Net-(C18-Pad-)") (class "Default")
      (node (ref "C18") (pin "-") (pinfunction "-_-") (pintype "passive"))
      (node (ref "C19") (pin "+") (pinfunction "+_+") (pintype "passive"))
      (node (ref "PWR1") (pin "3") (pinfunction "3_3") (pintype "passive"))
      (node (ref "PWR1") (pin "4") (pinfunction "4_4") (pintype "passive"))
      (node (ref "PWR1") (pin "5") (pinfunction "5_5") (pintype "passive"))
      (node (ref "PWR1") (pin "6") (pinfunction "6_6") (pintype "passive"))
      (node (ref "PWR1") (pin "7") (pinfunction "7_7") (pintype "passive"))
      (node (ref "PWR1") (pin "8") (pinfunction "8_8") (pintype "passive"))
    )
    (net (code "38") (name "Net-(D3-PadA)") (class "Default")
      (node (ref "D3") (pin "A") (pinfunction "A_A") (pintype "passive"))
      (node (ref "PWR1") (pin "10") (pinfunction "10_10") (pintype "passive"))
      (node (ref "PWR1") (pin "9") (pinfunction "9_9") (pintype "passive"))
    )
    (net (code "39") (name "Net-(D4-PadC)") (class "Default")
      (node (ref "D4") (pin "C") (pinfunction "C_C") (pintype "passive"))
      (node (ref "PWR1") (pin "1") (pinfunction "1_1") (pintype "passive"))
      (node (ref "PWR1") (pin "2") (pinfunction "2_2") (pintype "passive"))
    )
    (net (code "40") (name "Net-(IC1-PF0{slash}OSC_IN{slash}I2C2_SDA)") (class "Default")
      (node (ref "C3") (pin "2") (pinfunction "2_2") (pintype "passive"))
      (node (ref "IC1") (pin "5") (pinfunction "PF0/OSC_IN/I2C2_SDA_5") (pintype "bidirectional"))
      (node (ref "X1") (pin "P$2") (pinfunction "P$2_P$2") (pintype "bidirectional"))
    )
    (net (code "41") (name "Net-(IC1-PF1{slash}OSC_OUT{slash}I2C2_SCL)") (class "Default")
      (node (ref "C4") (pin "2") (pinfunction "2_2") (pintype "passive"))
      (node (ref "IC1") (pin "6") (pinfunction "PF1/OSC_OUT/I2C2_SCL_6") (pintype "bidirectional"))
      (node (ref "X1") (pin "P$1") (pinfunction "P$1_P$1") (pintype "bidirectional"))
    )
    (net (code "42") (name "Net-(IC2-CLR)") (class "Default")
      (node (ref "IC2") (pin "11") (pinfunction "CLR_11") (pintype "passive"))
      (node (ref "R6") (pin "1") (pinfunction "1_1") (pintype "passive"))
    )
    (net (code "43") (name "Net-(IC4A-+IN)") (class "Default")
      (node (ref "IC4") (pin "3") (pinfunction "+IN_3") (pintype "input"))
      (node (ref "R34") (pin "1") (pinfunction "1_1") (pintype "passive"))
    )
    (net (code "44") (name "Net-(IC4A--IN)") (class "Default")
      (node (ref "IC4") (pin "2") (pinfunction "-IN_2") (pintype "input"))
      (node (ref "R35") (pin "2") (pinfunction "2_2") (pintype "passive"))
      (node (ref "R36") (pin "1") (pinfunction "1_1") (pintype "passive"))
    )
    (net (code "45") (name "Net-(IC4A-OUT)") (class "Default")
      (node (ref "IC4") (pin "1") (pinfunction "OUT_1") (pintype "output"))
      (node (ref "R33") (pin "2") (pinfunction "2_2") (pintype "passive"))
      (node (ref "R35") (pin "1") (pinfunction "1_1") (pintype "passive"))
    )
    (net (code "46") (name "Net-(IC4B-+IN)") (class "Default")
      (node (ref "IC4") (pin "5") (pinfunction "+IN_5") (pintype "input"))
      (node (ref "R38") (pin "1") (pinfunction "1_1") (pintype "passive"))
    )
    (net (code "47") (name "Net-(IC4B--IN)") (class "Default")
      (node (ref "IC4") (pin "6") (pinfunction "-IN_6") (pintype "input"))
      (node (ref "R39") (pin "2") (pinfunction "2_2") (pintype "passive"))
      (node (ref "R40") (pin "1") (pinfunction "1_1") (pintype "passive"))
    )
    (net (code "48") (name "Net-(IC4B-OUT)") (class "Default")
      (node (ref "IC4") (pin "7") (pinfunction "OUT_7") (pintype "output"))
      (node (ref "R37") (pin "2") (pinfunction "2_2") (pintype "passive"))
      (node (ref "R39") (pin "1") (pinfunction "1_1") (pintype "passive"))
    )
    (net (code "49") (name "Net-(IC5-A)") (class "Default")
      (node (ref "D2") (pin "C") (pinfunction "C_C") (pintype "passive"))
      (node (ref "IC5") (pin "2") (pinfunction "A_2") (pintype "passive"))
      (node (ref "R17") (pin "2") (pinfunction "2_2") (pintype "passive"))
    )
    (net (code "50") (name "Net-(IC5-C)") (class "Default")
      (node (ref "D2") (pin "A") (pinfunction "A_A") (pintype "passive"))
      (node (ref "IC5") (pin "3") (pinfunction "C_3") (pintype "passive"))
      (node (ref "X21") (pin "5") (pinfunction "5_5") (pintype "passive"))
    )
    (net (code "51") (name "Net-(IC5-VB)") (class "Default")
      (node (ref "IC5") (pin "7") (pinfunction "VB_7") (pintype "passive"))
      (node (ref "R19") (pin "2") (pinfunction "2_2") (pintype "passive"))
    )
    (net (code "52") (name "Net-(IC7A-+IN)") (class "Default")
      (node (ref "IC7") (pin "3") (pinfunction "+IN_3") (pintype "input"))
      (node (ref "R26") (pin "1") (pinfunction "1_1") (pintype "passive"))
    )
    (net (code "53") (name "Net-(IC7A--IN)") (class "Default")
      (node (ref "IC7") (pin "2") (pinfunction "-IN_2") (pintype "input"))
      (node (ref "R27") (pin "2") (pinfunction "2_2") (pintype "passive"))
      (node (ref "R28") (pin "1") (pinfunction "1_1") (pintype "passive"))
    )
    (net (code "54") (name "Net-(IC7A-OUT)") (class "Default")
      (node (ref "IC7") (pin "1") (pinfunction "OUT_1") (pintype "output"))
      (node (ref "R15") (pin "2") (pinfunction "2_2") (pintype "passive"))
      (node (ref "R27") (pin "1") (pinfunction "1_1") (pintype "passive"))
    )
    (net (code "55") (name "Net-(IC7B-+IN)") (class "Default")
      (node (ref "IC7") (pin "5") (pinfunction "+IN_5") (pintype "input"))
      (node (ref "R30") (pin "1") (pinfunction "1_1") (pintype "passive"))
    )
    (net (code "56") (name "Net-(IC7B--IN)") (class "Default")
      (node (ref "IC7") (pin "6") (pinfunction "-IN_6") (pintype "input"))
      (node (ref "R31") (pin "2") (pinfunction "2_2") (pintype "passive"))
      (node (ref "R32") (pin "1") (pinfunction "1_1") (pintype "passive"))
    )
    (net (code "57") (name "Net-(IC7B-OUT)") (class "Default")
      (node (ref "IC7") (pin "7") (pinfunction "OUT_7") (pintype "output"))
      (node (ref "R29") (pin "2") (pinfunction "2_2") (pintype "passive"))
      (node (ref "R31") (pin "1") (pinfunction "1_1") (pintype "passive"))
    )
    (net (code "58") (name "Net-(IC10A-+IN)") (class "Default")
      (node (ref "IC10") (pin "3") (pinfunction "+IN_3") (pintype "input"))
      (node (ref "R23") (pin "1") (pinfunction "1_1") (pintype "passive"))
    )
    (net (code "59") (name "Net-(IC10A--IN)") (class "Default")
      (node (ref "IC10") (pin "2") (pinfunction "-IN_2") (pintype "input"))
      (node (ref "R24") (pin "2") (pinfunction "2_2") (pintype "passive"))
      (node (ref "R25") (pin "1") (pinfunction "1_1") (pintype "passive"))
    )
    (net (code "60") (name "Net-(IC10A-OUT)") (class "Default")
      (node (ref "IC10") (pin "1") (pinfunction "OUT_1") (pintype "output"))
      (node (ref "R10") (pin "2") (pinfunction "2_2") (pintype "passive"))
      (node (ref "R24") (pin "1") (pinfunction "1_1") (pintype "passive"))
    )
    (net (code "61") (name "Net-(IC10B-+IN)") (class "Default")
      (node (ref "IC10") (pin "5") (pinfunction "+IN_5") (pintype "input"))
      (node (ref "R12") (pin "1") (pinfunction "1_1") (pintype "passive"))
    )
    (net (code "62") (name "Net-(IC10B--IN)") (class "Default")
      (node (ref "IC10") (pin "6") (pinfunction "-IN_6") (pintype "input"))
      (node (ref "R13") (pin "2") (pinfunction "2_2") (pintype "passive"))
      (node (ref "R14") (pin "1") (pinfunction "1_1") (pintype "passive"))
    )
    (net (code "63") (name "Net-(IC10B-OUT)") (class "Default")
      (node (ref "IC10") (pin "7") (pinfunction "OUT_7") (pintype "output"))
      (node (ref "R11") (pin "2") (pinfunction "2_2") (pintype "passive"))
      (node (ref "R13") (pin "1") (pinfunction "1_1") (pintype "passive"))
    )
    (net (code "64") (name "Net-(R1-Pad2)") (class "Default")
      (node (ref "R1") (pin "2") (pinfunction "2_2") (pintype "passive"))
      (node (ref "R3") (pin "1") (pinfunction "1_1") (pintype "passive"))
      (node (ref "X2") (pin "3") (pinfunction "3_3") (pintype "passive"))
    )
    (net (code "65") (name "Net-(R2-Pad1)") (class "Default")
      (node (ref "R2") (pin "1") (pinfunction "1_1") (pintype "passive"))
      (node (ref "X2") (pin "2") (pinfunction "2_2") (pintype "passive"))
    )
    (net (code "66") (name "Net-(R16-Pad2)") (class "Default")
      (node (ref "R16") (pin "2") (pinfunction "2_2") (pintype "passive"))
      (node (ref "X22") (pin "5") (pinfunction "5_5") (pintype "passive"))
    )
    (net (code "67") (name "Net-(R17-Pad1)") (class "Default")
      (node (ref "R17") (pin "1") (pinfunction "1_1") (pintype "passive"))
      (node (ref "X21") (pin "4") (pinfunction "4_4") (pintype "passive"))
    )
    (net (code "68") (name "Net-(R18-Pad1)") (class "Default")
      (node (ref "R18") (pin "1") (pinfunction "1_1") (pintype "passive"))
      (node (ref "X22") (pin "4") (pinfunction "4_4") (pintype "passive"))
    )
    (net (code "69") (name "Net-(U2-GAIN)") (class "Default")
      (node (ref "R7") (pin "1") (pinfunction "1_1") (pintype "passive"))
      (node (ref "U2") (pin "8") (pinfunction "GAIN_8") (pintype "passive"))
    )
    (net (code "70") (name "Net-(X11-2)") (class "Default")
      (node (ref "R10") (pin "1") (pinfunction "1_1") (pintype "passive"))
      (node (ref "X11") (pin "P$1") (pinfunction "2_P$1") (pintype "passive"))
    )
    (net (code "71") (name "Net-(X12-2)") (class "Default")
      (node (ref "R11") (pin "1") (pinfunction "1_1") (pintype "passive"))
      (node (ref "X12") (pin "P$1") (pinfunction "2_P$1") (pintype "passive"))
    )
    (net (code "72") (name "Net-(X13-2)") (class "Default")
      (node (ref "R15") (pin "1") (pinfunction "1_1") (pintype "passive"))
      (node (ref "X13") (pin "P$1") (pinfunction "2_P$1") (pintype "passive"))
    )
    (net (code "73") (name "Net-(X14-2)") (class "Default")
      (node (ref "R29") (pin "1") (pinfunction "1_1") (pintype "passive"))
      (node (ref "X14") (pin "P$1") (pinfunction "2_P$1") (pintype "passive"))
    )
    (net (code "74") (name "Net-(X15-2)") (class "Default")
      (node (ref "R33") (pin "1") (pinfunction "1_1") (pintype "passive"))
      (node (ref "X15") (pin "P$1") (pinfunction "2_P$1") (pintype "passive"))
    )
    (net (code "75") (name "Net-(X16-2)") (class "Default")
      (node (ref "R37") (pin "1") (pinfunction "1_1") (pintype "passive"))
      (node (ref "X16") (pin "P$1") (pinfunction "2_P$1") (pintype "passive"))
    )
    (net (code "76") (name "RST") (class "Default")
      (node (ref "C6") (pin "1") (pinfunction "1_1") (pintype "passive"))
      (node (ref "IC1") (pin "7") (pinfunction "NRST_7") (pintype "bidirectional"))
      (node (ref "J1") (pin "10") (pinfunction "~{RESET}_10") (pintype "bidirectional"))
      (node (ref "R4") (pin "1") (pinfunction "1_1") (pintype "passive"))
    )
    (net (code "77") (name "RST_DAC0") (class "Default")
      (node (ref "IC1") (pin "19") (pinfunction "PB1/TIM3_CH4/ADC_IN9/SDADC1_AIN5P/SDADC1_AIN6M_19") (pintype "bidirectional"))
      (node (ref "U2") (pin "17") (pinfunction "~{RESET}_17") (pintype "passive"))
    )
    (net (code "78") (name "RST_OLED") (class "Default")
      (node (ref "D1") (pin "RES") (pinfunction "RES_RES") (pintype "input"))
      (node (ref "IC1") (pin "18") (pinfunction "PB0/SPI1_MOSI/I2S1_SD/TIM3_CH3/ADC_IN8/SDADC1_AIN6P_18") (pintype "bidirectional"))
    )
    (net (code "79") (name "RST_USB") (class "Default")
      (node (ref "IC1") (pin "42") (pinfunction "PB6/I2C1_SCL/USART1_TX/TIM4_CH1_42") (pintype "bidirectional"))
    )
    (net (code "80") (name "SCK") (class "Default")
      (node (ref "D1") (pin "CLK") (pinfunction "CLK_CLK") (pintype "input"))
      (node (ref "IC1") (pin "45") (pinfunction "PB8/SPI2_SCK/I2S2_CK/I2C1_SCL/USART3_TX/CAN_RX/TIM4_CH3_45") (pintype "bidirectional"))
      (node (ref "IC2") (pin "8") (pinfunction "SCLK_8") (pintype "passive"))
      (node (ref "U2") (pin "6") (pinfunction "SCLK_6") (pintype "passive"))
    )
    (net (code "81") (name "SDC_OLED") (class "Default")
      (node (ref "D1") (pin "SDC") (pinfunction "SDC_SDC") (pintype "bidirectional"))
      (node (ref "IC1") (pin "46") (pinfunction "PB9/SPI2_NSS/I2S2_WS/I2C1_SDA/USART3_RX/CAN_TX/TIM4_CH4_46") (pintype "bidirectional"))
    )
    (net (code "82") (name "SS_DAC0") (class "Default")
      (node (ref "IC1") (pin "40") (pinfunction "PB4/SPI1_MISO/I2S1_MCK/SPI3_MISO/I2S3_MCK/USART2_RX/TIM3_CH1/NJTRST_40") (pintype "bidirectional"))
      (node (ref "U2") (pin "5") (pinfunction "~{SYNC}_5") (pintype "passive"))
    )
    (net (code "83") (name "SS_DAC1") (class "Default")
      (node (ref "IC1") (pin "41") (pinfunction "PB5/SPI1_MOSI/I2S1_SD/SPI3_MOSI/I2S3_SD/I2C1_SMBAI/USART2_CK/TIM3_CH2_41") (pintype "bidirectional"))
      (node (ref "IC2") (pin "7") (pinfunction "SYNC_7") (pintype "passive"))
    )
    (net (code "84") (name "SS_OLED") (class "Default")
      (node (ref "D1") (pin "CCS") (pinfunction "CCS_CCS") (pintype "input"))
      (node (ref "IC1") (pin "20") (pinfunction "PB2/SDADC1_AIN4P/SDADC2_AIN6P_20") (pintype "bidirectional"))
      (node (ref "R5") (pin "1") (pinfunction "1_1") (pintype "passive"))
    )
    (net (code "85") (name "SS_USB") (class "Default")
      (node (ref "IC1") (pin "43") (pinfunction "PB7/I2C1_SDA/USART1_RX/TIM4_CH2_43") (pintype "bidirectional"))
    )
    (net (code "86") (name "USB_PER_D_N") (class "Default")
      (node (ref "IC1") (pin "32") (pinfunction "PA11/SPI2_NSS/I2S2_WS/SPI1_NSS/I2S1_WS/USART1_CTS/CAN_RX/TIM4_CH1/TIM5_CH2_32") (pintype "bidirectional"))
      (node (ref "R2") (pin "2") (pinfunction "2_2") (pintype "passive"))
    )
    (net (code "87") (name "USB_PER_D_P") (class "Default")
      (node (ref "IC1") (pin "33") (pinfunction "PA12/SPI1_SCK/I2S1_CK/USART1_RTS/CAN_TX/TIM4_CH2/TIM5_CH3_33") (pintype "bidirectional"))
      (node (ref "R3") (pin "2") (pinfunction "2_2") (pintype "passive"))
    )
    (net (code "88") (name "unconnected-(IC1-PA6{slash}SPI1_MISO{slash}I2S1_MCK{slash}TIM3_CH1{slash}ADC_IN6{slash}DAC2_OUT1-Pad16)") (class "Default")
      (node (ref "IC1") (pin "16") (pinfunction "PA6/SPI1_MISO/I2S1_MCK/TIM3_CH1/ADC_IN6/DAC2_OUT1_16") (pintype "bidirectional"))
    )
    (net (code "89") (name "unconnected-(IC1-PA8{slash}SPI2_SCK{slash}I2S2_CK{slash}I2C2_SMBA{slash}USART1_CK{slash}TIM5_CH1-Pad29)") (class "Default")
      (node (ref "IC1") (pin "29") (pinfunction "PA8/SPI2_SCK/I2S2_CK/I2C2_SMBA/USART1_CK/TIM5_CH1_29") (pintype "bidirectional"))
    )
    (net (code "90") (name "unconnected-(IC1-PD8{slash}SPI2_SCK{slash}I2S2_CK{slash}USART3_TX{slash}SDADC3_AIN6P-Pad28)") (class "Default")
      (node (ref "IC1") (pin "28") (pinfunction "PD8/SPI2_SCK/I2S2_CK/USART3_TX/SDADC3_AIN6P_28") (pintype "bidirectional"))
    )
    (net (code "91") (name "unconnected-(IC1-PE9{slash}SDADC1_AIN7P{slash}SDADC1_AIN8M{slash}SDADC2_AIN7P{slash}SDADC2_AIN8M-Pad22)") (class "Default")
      (node (ref "IC1") (pin "22") (pinfunction "PE9/SDADC1_AIN7P/SDADC1_AIN8M/SDADC2_AIN7P/SDADC2_AIN8M_22") (pintype "bidirectional"))
    )
    (net (code "92") (name "unconnected-(IC1-PF6{slash}SPI1_MOSI{slash}I2S1_SD{slash}USART3_RTS{slash}TIM4_CH4{slash}I2C2_SCL-Pad35)") (class "Default")
      (node (ref "IC1") (pin "35") (pinfunction "PF6/SPI1_MOSI/I2S1_SD/USART3_RTS/TIM4_CH4/I2C2_SCL_35") (pintype "bidirectional"))
    )
    (net (code "93") (name "unconnected-(IC1-PF7{slash}I2C2_SDA{slash}USART2_CK-Pad36)") (class "Default")
      (node (ref "IC1") (pin "36") (pinfunction "PF7/I2C2_SDA/USART2_CK_36") (pintype "bidirectional"))
    )
    (net (code "94") (name "unconnected-(IC2-NC-Pad2)") (class "Default")
      (node (ref "IC2") (pin "2") (pinfunction "NC_2") (pintype "passive"))
    )
    (net (code "95") (name "unconnected-(IC2-NC_2-Pad13)") (class "Default")
      (node (ref "IC2") (pin "13") (pinfunction "NC_2_13") (pintype "passive"))
    )
    (net (code "96") (name "unconnected-(IC2-NC_3-Pad6)") (class "Default")
      (node (ref "IC2") (pin "6") (pinfunction "NC_3_6") (pintype "passive"))
    )
    (net (code "97") (name "unconnected-(IC2-NC_4-Pad12)") (class "Default")
      (node (ref "IC2") (pin "12") (pinfunction "NC_4_12") (pintype "passive"))
    )
    (net (code "98") (name "unconnected-(IC2-SDO-Pad16)") (class "Default")
      (node (ref "IC2") (pin "16") (pinfunction "SDO_16") (pintype "passive"))
    )
    (net (code "99") (name "unconnected-(IC8-COMP-Pad7)") (class "Default")
      (node (ref "IC8") (pin "7") (pinfunction "COMP_7") (pintype "bidirectional"))
    )
    (net (code "100") (name "unconnected-(IC8-DNC-Pad1)") (class "Default")
      (node (ref "IC8") (pin "1") (pinfunction "DNC_1") (pintype "no_connect"))
    )
    (net (code "101") (name "unconnected-(IC8-DNC2-Pad8)") (class "Default")
      (node (ref "IC8") (pin "8") (pinfunction "DNC2_8") (pintype "no_connect"))
    )
    (net (code "102") (name "unconnected-(IC8-NIC-Pad3)") (class "Default")
      (node (ref "IC8") (pin "3") (pinfunction "NIC_3") (pintype "no_connect"))
    )
    (net (code "103") (name "unconnected-(IC8-TRIM-Pad5)") (class "Default")
      (node (ref "IC8") (pin "5") (pinfunction "TRIM_5") (pintype "bidirectional"))
    )
    (net (code "104") (name "unconnected-(IC9-COMP-Pad7)") (class "Default")
      (node (ref "IC9") (pin "7") (pinfunction "COMP_7") (pintype "bidirectional"))
    )
    (net (code "105") (name "unconnected-(IC9-DNC-Pad1)") (class "Default")
      (node (ref "IC9") (pin "1") (pinfunction "DNC_1") (pintype "no_connect"))
    )
    (net (code "106") (name "unconnected-(IC9-DNC2-Pad8)") (class "Default")
      (node (ref "IC9") (pin "8") (pinfunction "DNC2_8") (pintype "no_connect"))
    )
    (net (code "107") (name "unconnected-(IC9-NIC-Pad3)") (class "Default")
      (node (ref "IC9") (pin "3") (pinfunction "NIC_3") (pintype "no_connect"))
    )
    (net (code "108") (name "unconnected-(IC9-TRIM-Pad5)") (class "Default")
      (node (ref "IC9") (pin "5") (pinfunction "TRIM_5") (pintype "bidirectional"))
    )
    (net (code "109") (name "unconnected-(J1-KEY-Pad7)") (class "Default")
      (node (ref "J1") (pin "7") (pinfunction "KEY_7") (pintype "bidirectional"))
    )
    (net (code "110") (name "unconnected-(U2-SDO-Pad16)") (class "Default")
      (node (ref "U2") (pin "16") (pinfunction "SDO_16") (pintype "passive"))
    )
    (net (code "111") (name "unconnected-(X2-Pad1)") (class "Default")
      (node (ref "X2") (pin "1") (pinfunction "1_1") (pintype "passive"))
    )
    (net (code "112") (name "unconnected-(X3-3-PadP$2)") (class "Default")
      (node (ref "X3") (pin "P$2") (pinfunction "3_P$2") (pintype "passive"))
    )
    (net (code "113") (name "unconnected-(X4-3-PadP$2)") (class "Default")
      (node (ref "X4") (pin "P$2") (pinfunction "3_P$2") (pintype "passive"))
    )
    (net (code "114") (name "unconnected-(X5-3-PadP$2)") (class "Default")
      (node (ref "X5") (pin "P$2") (pinfunction "3_P$2") (pintype "passive"))
    )
    (net (code "115") (name "unconnected-(X6-3-PadP$2)") (class "Default")
      (node (ref "X6") (pin "P$2") (pinfunction "3_P$2") (pintype "passive"))
    )
    (net (code "116") (name "unconnected-(X7-3-PadP$2)") (class "Default")
      (node (ref "X7") (pin "P$2") (pinfunction "3_P$2") (pintype "passive"))
    )
    (net (code "117") (name "unconnected-(X8-3-PadP$2)") (class "Default")
      (node (ref "X8") (pin "P$2") (pinfunction "3_P$2") (pintype "passive"))
    )
    (net (code "118") (name "unconnected-(X9-3-PadP$2)") (class "Default")
      (node (ref "X9") (pin "P$2") (pinfunction "3_P$2") (pintype "passive"))
    )
    (net (code "119") (name "unconnected-(X10-3-PadP$2)") (class "Default")
      (node (ref "X10") (pin "P$2") (pinfunction "3_P$2") (pintype "passive"))
    )
    (net (code "120") (name "unconnected-(X11-3-PadP$2)") (class "Default")
      (node (ref "X11") (pin "P$2") (pinfunction "3_P$2") (pintype "passive"))
    )
    (net (code "121") (name "unconnected-(X12-3-PadP$2)") (class "Default")
      (node (ref "X12") (pin "P$2") (pinfunction "3_P$2") (pintype "passive"))
    )
    (net (code "122") (name "unconnected-(X13-3-PadP$2)") (class "Default")
      (node (ref "X13") (pin "P$2") (pinfunction "3_P$2") (pintype "passive"))
    )
    (net (code "123") (name "unconnected-(X14-3-PadP$2)") (class "Default")
      (node (ref "X14") (pin "P$2") (pinfunction "3_P$2") (pintype "passive"))
    )
    (net (code "124") (name "unconnected-(X15-3-PadP$2)") (class "Default")
      (node (ref "X15") (pin "P$2") (pinfunction "3_P$2") (pintype "passive"))
    )
    (net (code "125") (name "unconnected-(X16-3-PadP$2)") (class "Default")
      (node (ref "X16") (pin "P$2") (pinfunction "3_P$2") (pintype "passive"))
    )
    (net (code "126") (name "unconnected-(X17-3-PadP$2)") (class "Default")
      (node (ref "X17") (pin "P$2") (pinfunction "3_P$2") (pintype "passive"))
    )
    (net (code "127") (name "unconnected-(X18-3-PadP$2)") (class "Default")
      (node (ref "X18") (pin "P$2") (pinfunction "3_P$2") (pintype "passive"))
    )
    (net (code "128") (name "unconnected-(X19-3-PadP$2)") (class "Default")
      (node (ref "X19") (pin "P$2") (pinfunction "3_P$2") (pintype "passive"))
    )
    (net (code "129") (name "unconnected-(X20-3-PadP$2)") (class "Default")
      (node (ref "X20") (pin "P$2") (pinfunction "3_P$2") (pintype "passive"))
    )
    (net (code "130") (name "unconnected-(X21-Pad1)") (class "Default")
      (node (ref "X21") (pin "1") (pinfunction "1_1") (pintype "passive"))
    )
    (net (code "131") (name "unconnected-(X21-Pad2)") (class "Default")
      (node (ref "X21") (pin "2") (pinfunction "2_2") (pintype "passive"))
    )
    (net (code "132") (name "unconnected-(X21-Pad3)") (class "Default")
      (node (ref "X21") (pin "3") (pinfunction "3_3") (pintype "passive"))
    )
    (net (code "133") (name "unconnected-(X22-Pad1)") (class "Default")
      (node (ref "X22") (pin "1") (pinfunction "1_1") (pintype "passive"))
    )
    (net (code "134") (name "unconnected-(X22-Pad3)") (class "Default")
      (node (ref "X22") (pin "3") (pinfunction "3_3") (pintype "passive"))
    )
  )
)
